# Microcontroller.net
KiCad netlist of a schematic drawn in Altium Designer
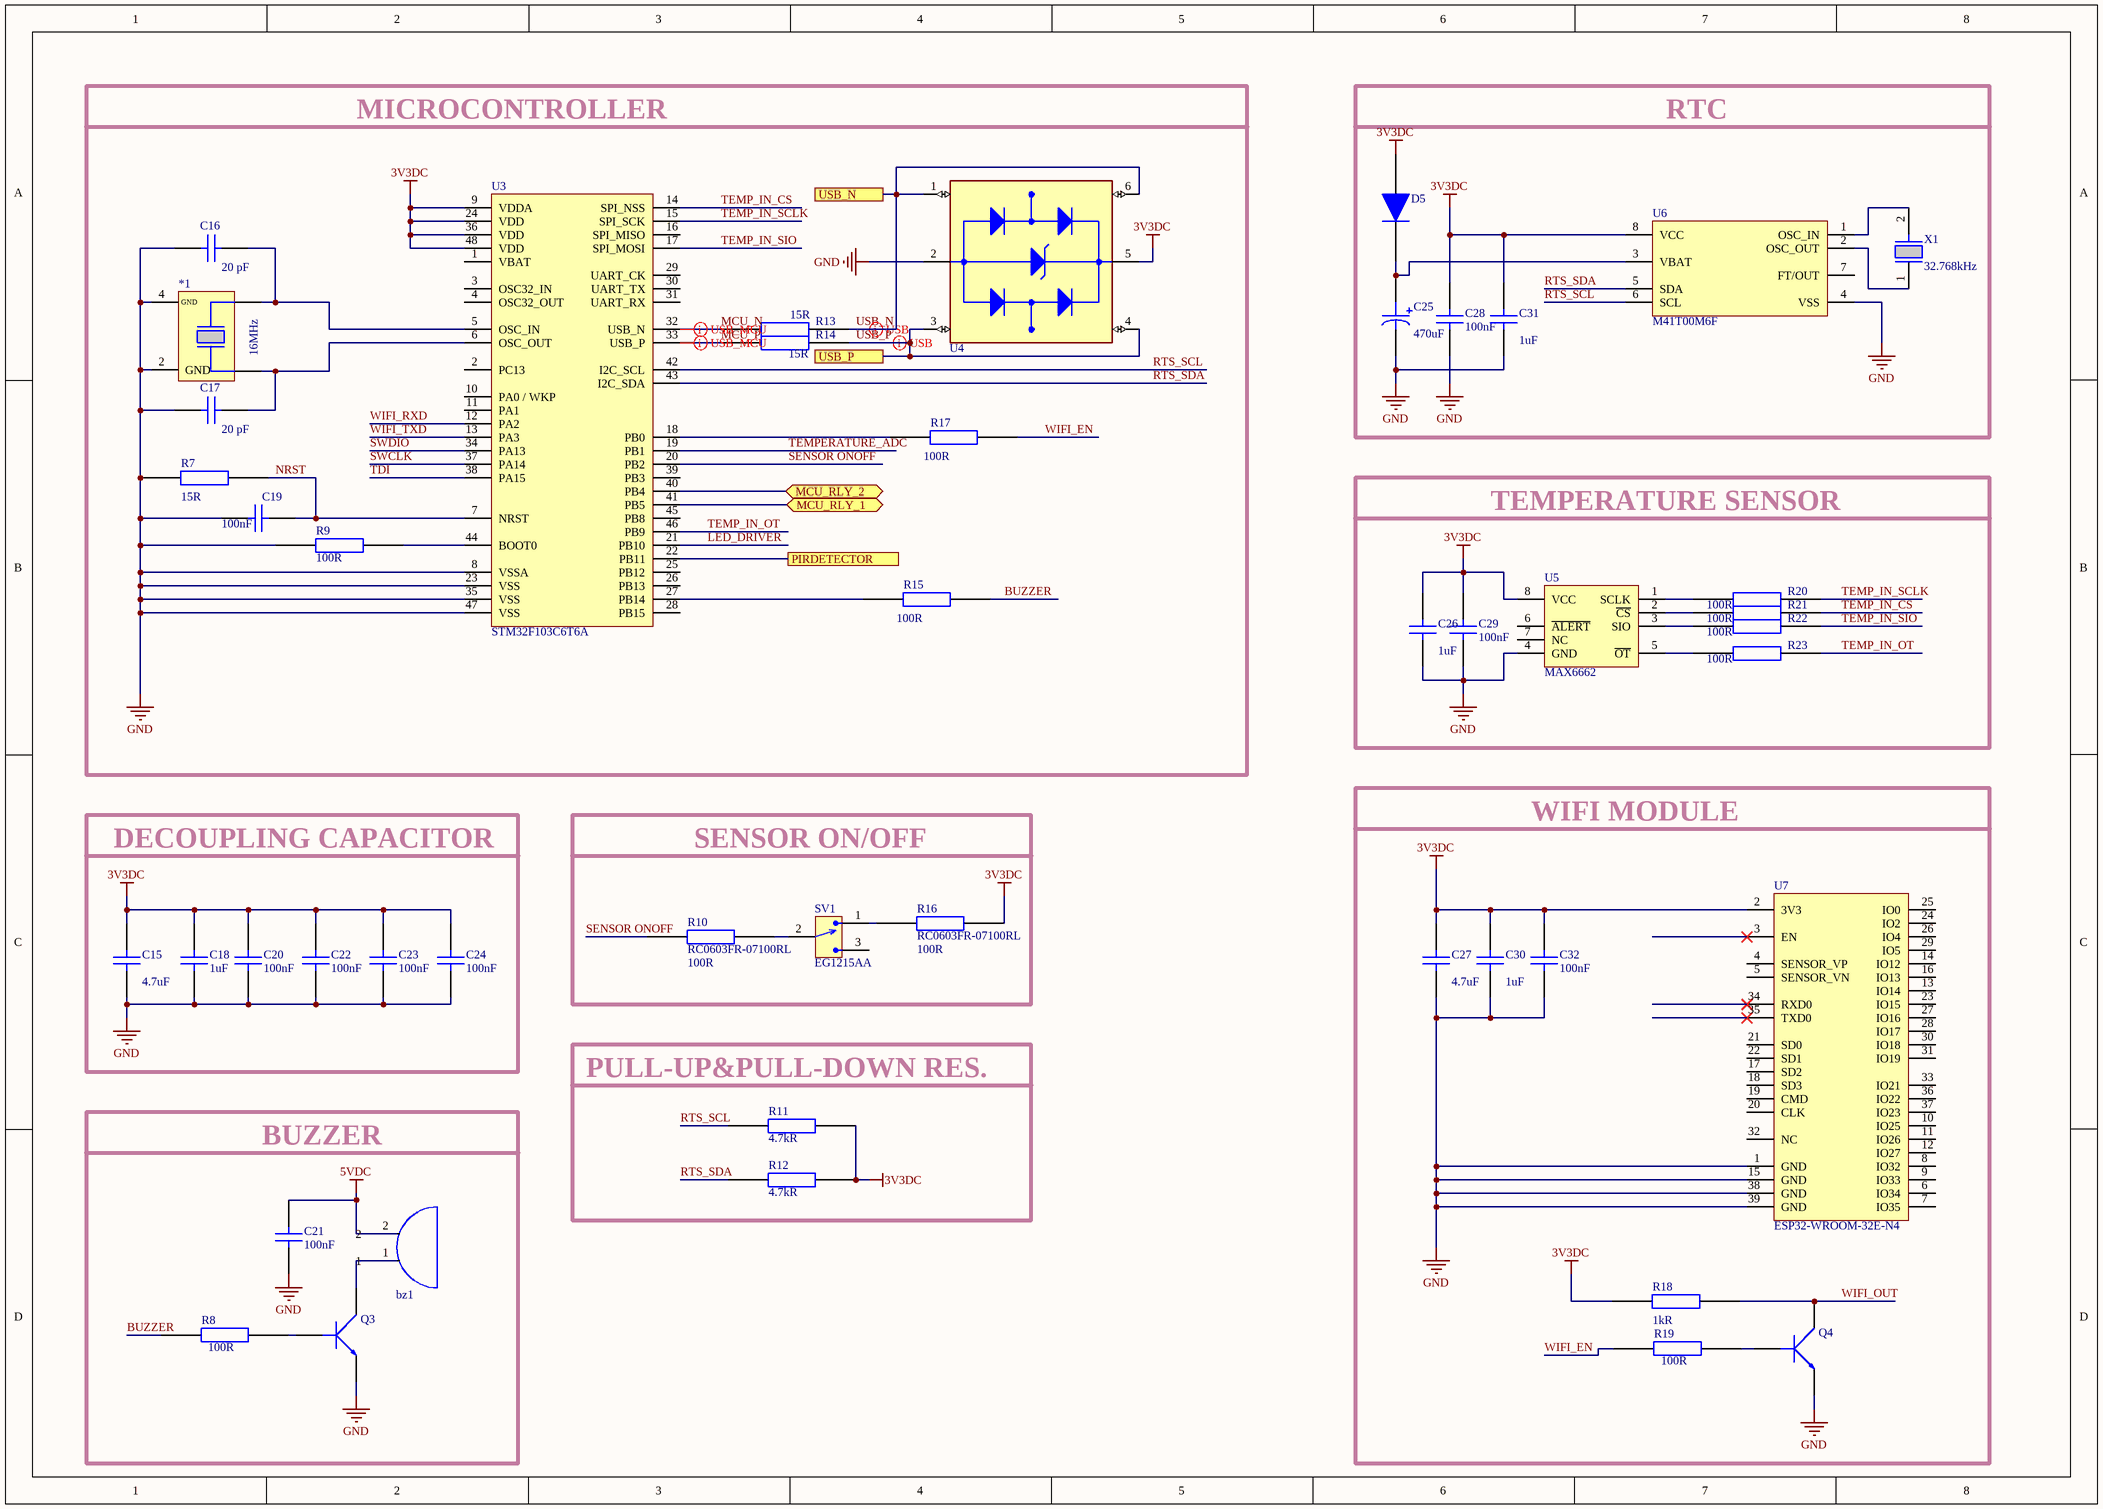
[diagram p0: Microcontroller.SchDoc]

(export (version "E")
  (design (tool "Eeschema 10.0.6"))
  (components
    (comp (ref "*1")
      (value "CRYSTAL 16MHz")
      (footprint "ECS")
      (description "Crystal 16MHz ±30ppm (Tol) ±50ppm (Stability) 20pF FUND 50Ohm 4-Pin Mini-SMD T/R")
      (fields
        (field (name "MANUFACTURER") "ECS International")
        (field (name "MANUFACTURER PART NUMBER") "ECS-160-20-30B-TR")
        (field (name "FREQUENCY") "16MHz")
        (field (name "DESIGNED BY") "Selenay")
      )
      (libsource (lib "LIBRARY1") (part "CRYSTAL 16MHz"))
    )
    (comp (ref "bz1")
      (value "2223-CMI-9605IC-0580T-ND")
      (footprint "CMI-9605IC")
      (description "Audio Buzzer Magnetic 3VDC 7VDC 30mA 5VDC 85dB 2600Hz to 2800Hz Through Hole Pin Box")
      (fields
        (field (name "MANUFACTURER") "CUI Devices")
        (field (name "MANUFACTURER PART NUMBER") "CMI-9605IC-0580T")
        (field (name "DESIGNED BY") "Selenay")
      )
      (libsource (lib "LIBRARY1") (part "2223-CMI-9605IC-0580T-ND"))
    )
    (comp (ref "C15")
      (value "4.7uF")
      (footprint "CAP_0805")
      (description "Multilayer Ceramic Capacitor, 4.7 uF, 25 V, ± 10%")
      (fields
        (field (name "MANUFACTURER") "Samsung")
        (field (name "MANUFACTURER PART NUMBER") "CL21A475KAQNNNE")
        (field (name "DESIGNED BY") "Selenay")
      )
      (libsource (lib "LIBRARY1") (part "CAP CER 4.7uF 0805"))
    )
    (comp (ref "C16")
      (value "CL10C200JB8NNNC")
      (footprint "CAP_0603")
      (description "Multilayer Ceramic Capacitor, 20 pF, 50 V, ± 5%")
      (fields
        (field (name "MANUFACTURER") "Samsung")
        (field (name "CAPATICANCE") "20 pF")
        (field (name "DESIGNED BY") "Selenay")
      )
      (libsource (lib "LIBRARY1") (part "CAP CER 20pF 0603"))
    )
    (comp (ref "C17")
      (value "CL10C200JB8NNNC")
      (footprint "CAP_0603")
      (description "Multilayer Ceramic Capacitor, 20 pF, 50 V, ± 5%")
      (fields
        (field (name "MANUFACTURER") "Samsung")
        (field (name "CAPATICANCE") "20 pF")
        (field (name "DESIGNED BY") "Selenay")
      )
      (libsource (lib "LIBRARY1") (part "CAP CER 20pF 0603"))
    )
    (comp (ref "C18")
      (value "1uF")
      (footprint "CAP_0805")
      (description "Multilayer Ceramic Capacitor, 1 uF, 50 V, ± 10%, X7R, 0805 [2012 Metric]")
      (fields
        (field (name "MANUFACTURER") "Samsung")
        (field (name "MANUFACTURER PART NUMBER") "CL21B105KBFNNNE")
        (field (name "DESIGNED BY") "Selenay")
      )
      (libsource (lib "LIBRARY1") (part "CAP CER 1uF 0805"))
    )
    (comp (ref "C19")
      (value "100nF")
      (footprint "CAP_0603")
      (description "Multilayer Ceramic Capacitor, 0.1 uF, 50 V, ± 10%, X7R, 0603 [1608 Metric]")
      (fields
        (field (name "MANUFACTURER") "KEMET")
        (field (name "MANUFACTURER PART NUMBER") "C0603C104K5RACTU")
        (field (name "DESIGNED BY") "Selenay")
      )
      (libsource (lib "LIBRARY1") (part "CAP CER 100nF 0603"))
    )
    (comp (ref "C20")
      (value "100nF")
      (footprint "CAP_0603")
      (description "Multilayer Ceramic Capacitor, 0.1 uF, 50 V, ± 10%, X7R, 0603 [1608 Metric]")
      (fields
        (field (name "MANUFACTURER") "KEMET")
        (field (name "MANUFACTURER PART NUMBER") "C0603C104K5RACTU")
        (field (name "DESIGNED BY") "Selenay")
      )
      (libsource (lib "LIBRARY1") (part "CAP CER 100nF 0603"))
    )
    (comp (ref "C21")
      (value "100nF")
      (footprint "CAP_0603")
      (description "Multilayer Ceramic Capacitor, 0.1 uF, 50 V, ± 10%, X7R, 0603 [1608 Metric]")
      (fields
        (field (name "MANUFACTURER") "KEMET")
        (field (name "MANUFACTURER PART NUMBER") "C0603C104K5RACTU")
        (field (name "DESIGNED BY") "Selenay")
      )
      (libsource (lib "LIBRARY1") (part "CAP CER 100nF 0603"))
    )
    (comp (ref "C22")
      (value "100nF")
      (footprint "CAP_0603")
      (description "Multilayer Ceramic Capacitor, 0.1 uF, 50 V, ± 10%, X7R, 0603 [1608 Metric]")
      (fields
        (field (name "MANUFACTURER") "KEMET")
        (field (name "MANUFACTURER PART NUMBER") "C0603C104K5RACTU")
        (field (name "DESIGNED BY") "Selenay")
      )
      (libsource (lib "LIBRARY1") (part "CAP CER 100nF 0603"))
    )
    (comp (ref "C23")
      (value "100nF")
      (footprint "CAP_0603")
      (description "Multilayer Ceramic Capacitor, 0.1 uF, 50 V, ± 10%, X7R, 0603 [1608 Metric]")
      (fields
        (field (name "MANUFACTURER") "KEMET")
        (field (name "MANUFACTURER PART NUMBER") "C0603C104K5RACTU")
        (field (name "DESIGNED BY") "Selenay")
      )
      (libsource (lib "LIBRARY1") (part "CAP CER 100nF 0603"))
    )
    (comp (ref "C24")
      (value "100nF")
      (footprint "CAP_0603")
      (description "Multilayer Ceramic Capacitor, 0.1 uF, 50 V, ± 10%, X7R, 0603 [1608 Metric]")
      (fields
        (field (name "MANUFACTURER") "KEMET")
        (field (name "MANUFACTURER PART NUMBER") "C0603C104K5RACTU")
        (field (name "DESIGNED BY") "Selenay")
      )
      (libsource (lib "LIBRARY1") (part "CAP CER 100nF 0603"))
    )
    (comp (ref "C25")
      (value "470uF")
      (footprint "CAP_EEVSRIES")
      (description "Cap Aluminum Lytic 470uF 25V 20% (10 X 10.2mm) SMD 850mA 2000h 105C T/R")
      (fields
        (field (name "MANUFACTURER") "KEMET")
        (field (name "MANUFACTURER PART NUMBER") "EEV477M025A9PAA")
        (field (name "DESIGNED BY") "Selenay")
      )
      (libsource (lib "LIBRARY1") (part "CAP ALU 470uF"))
    )
    (comp (ref "C26")
      (value "1uF")
      (footprint "CAP_0805")
      (description "Multilayer Ceramic Capacitor, 1 uF, 50 V, ± 10%, X7R, 0805 [2012 Metric]")
      (fields
        (field (name "MANUFACTURER") "Samsung")
        (field (name "MANUFACTURER PART NUMBER") "CL21B105KBFNNNE")
        (field (name "DESIGNED BY") "Selenay")
      )
      (libsource (lib "LIBRARY1") (part "CAP CER 1uF 0805"))
    )
    (comp (ref "C27")
      (value "4.7uF")
      (footprint "CAP_0805")
      (description "Multilayer Ceramic Capacitor, 4.7 uF, 25 V, ± 10%")
      (fields
        (field (name "MANUFACTURER") "Samsung")
        (field (name "MANUFACTURER PART NUMBER") "CL21A475KAQNNNE")
        (field (name "DESIGNED BY") "Selenay")
      )
      (libsource (lib "LIBRARY1") (part "CAP CER 4.7uF 0805"))
    )
    (comp (ref "C28")
      (value "100nF")
      (footprint "CAP_0603")
      (description "Multilayer Ceramic Capacitor, 0.1 uF, 50 V, ± 10%, X7R, 0603 [1608 Metric]")
      (fields
        (field (name "MANUFACTURER") "KEMET")
        (field (name "MANUFACTURER PART NUMBER") "C0603C104K5RACTU")
        (field (name "DESIGNED BY") "Selenay")
      )
      (libsource (lib "LIBRARY1") (part "CAP CER 100nF 0603"))
    )
    (comp (ref "C29")
      (value "100nF")
      (footprint "CAP_0603")
      (description "Multilayer Ceramic Capacitor, 0.1 uF, 50 V, ± 10%, X7R, 0603 [1608 Metric]")
      (fields
        (field (name "MANUFACTURER") "KEMET")
        (field (name "MANUFACTURER PART NUMBER") "C0603C104K5RACTU")
        (field (name "DESIGNED BY") "Selenay")
      )
      (libsource (lib "LIBRARY1") (part "CAP CER 100nF 0603"))
    )
    (comp (ref "C30")
      (value "1uF")
      (footprint "CAP_0805")
      (description "Multilayer Ceramic Capacitor, 1 uF, 50 V, ± 10%, X7R, 0805 [2012 Metric]")
      (fields
        (field (name "MANUFACTURER") "Samsung")
        (field (name "MANUFACTURER PART NUMBER") "CL21B105KBFNNNE")
        (field (name "DESIGNED BY") "Selenay")
      )
      (libsource (lib "LIBRARY1") (part "CAP CER 1uF 0805"))
    )
    (comp (ref "C31")
      (value "1uF")
      (footprint "CAP_0805")
      (description "Multilayer Ceramic Capacitor, 1 uF, 50 V, ± 10%, X7R, 0805 [2012 Metric]")
      (fields
        (field (name "MANUFACTURER") "Samsung")
        (field (name "MANUFACTURER PART NUMBER") "CL21B105KBFNNNE")
        (field (name "DESIGNED BY") "Selenay")
      )
      (libsource (lib "LIBRARY1") (part "CAP CER 1uF 0805"))
    )
    (comp (ref "C32")
      (value "100nF")
      (footprint "CAP_0603")
      (description "Multilayer Ceramic Capacitor, 0.1 uF, 50 V, ± 10%, X7R, 0603 [1608 Metric]")
      (fields
        (field (name "MANUFACTURER") "KEMET")
        (field (name "MANUFACTURER PART NUMBER") "C0603C104K5RACTU")
        (field (name "DESIGNED BY") "Selenay")
      )
      (libsource (lib "LIBRARY1") (part "CAP CER 100nF 0603"))
    )
    (comp (ref "D5")
      (value "1N4148WS-7-F")
      (footprint "SOD323F")
      (description "Small Signal Diode, 100V, SOD-323")
      (fields (field (name "MANUFACTURER") "Diodes") (field (name "VOLTAGE") "75V"))
      (libsource (lib "LIBRARY1") (part "1N4148WS"))
    )
    (comp (ref "Q3")
      (value "MMBT3904-7-F")
      (footprint "SOT-23F")
      (description "Transistor General Purpose BJT NPN 40 Volt 0.2A Automotive 3-Pin SOT-23")
      (fields (field (name "MANUFACTURER") "Diodes Zetex") (field (name "DESIGNED BY") "Selenay"))
      (libsource (lib "LIBRARY1") (part "MMBT3904-7-F"))
    )
    (comp (ref "Q4")
      (value "MMBT3904-7-F")
      (footprint "SOT-23F")
      (description "Transistor General Purpose BJT NPN 40 Volt 0.2A Automotive 3-Pin SOT-23")
      (fields (field (name "MANUFACTURER") "Diodes Zetex") (field (name "DESIGNED BY") "Selenay"))
      (libsource (lib "LIBRARY1") (part "MMBT3904-7-F"))
    )
    (comp (ref "R7")
      (value "15R")
      (footprint "RES_0603")
      (description "SMD Chip Resistor, 15 Ohm, ± 1%, 100 mW, 0603")
      (fields
        (field (name "MANUFACTURER") "Yageo")
        (field (name "MANUFACTURER PART NUMBER") "RC0603FR-0715RL")
        (field (name "DESIGNED BY") "Selenay")
      )
      (libsource (lib "LIBRARY1") (part "RES 15 OHM 0603"))
    )
    (comp (ref "R8")
      (value "100R")
      (footprint "RES_0603")
      (description "SMD Chip Resistor, 100 Ohm, ± 1%, 100 mW, 0603")
      (fields
        (field (name "MANUFACTURER") "Yageo")
        (field (name "MANUFACTURER PART NUMBER") "RC0603FR-07100RL")
        (field (name "DESIGNED BY") "Selenay")
      )
      (libsource (lib "LIBRARY1") (part "RES 100 OHM 0603"))
    )
    (comp (ref "R9")
      (value "100R")
      (footprint "RES_0603")
      (description "SMD Chip Resistor, 100 Ohm, ± 1%, 100 mW, 0603")
      (fields
        (field (name "MANUFACTURER") "Yageo")
        (field (name "MANUFACTURER PART NUMBER") "RC0603FR-07100RL")
        (field (name "DESIGNED BY") "Selenay")
      )
      (libsource (lib "") (part "RES 100 OHM 0603_1"))
    )
    (comp (ref "R10")
      (value "RC0603FR-07100RL")
      (footprint "RES_0603")
      (description "SMD Chip Resistor, 100 Ohm, ± 1%, 100 mW, 0603")
      (fields
        (field (name "MANUFACTURER") "Yageo")
        (field (name "TOLERANCE") "1%")
        (field (name "ALTIUM_VALUE") "100R")
        (field (name "DESIGNED BY") "Selenay")
      )
      (libsource (lib "") (part "RES 100 OHM 0603_1"))
    )
    (comp (ref "R11")
      (value "4.7kR")
      (footprint "RES_0603")
      (description "SMD Chip Resistor, 4.7 kOhm, ± 1%, 100 mW, 0603 [1608 Metric], Thick Film, General Purpose")
      (fields
        (field (name "MANUFACTURER") "Yageo")
        (field (name "MANUFACTURER PART NUMBER") "RC0603FR-074K7L")
      )
      (libsource (lib "LIBRARY1") (part "RES 4.7K OHM 0603"))
    )
    (comp (ref "R12")
      (value "4.7kR")
      (footprint "RES_0603")
      (description "SMD Chip Resistor, 4.7 kOhm, ± 1%, 100 mW, 0603 [1608 Metric], Thick Film, General Purpose")
      (fields
        (field (name "MANUFACTURER") "Yageo")
        (field (name "MANUFACTURER PART NUMBER") "RC0603FR-074K7L")
      )
      (libsource (lib "LIBRARY1") (part "RES 4.7K OHM 0603"))
    )
    (comp (ref "R13")
      (value "15R")
      (footprint "RES_0603")
      (description "SMD Chip Resistor, 15 Ohm, ± 1%, 100 mW, 0603")
      (fields
        (field (name "MANUFACTURER") "Yageo")
        (field (name "MANUFACTURER PART NUMBER") "RC0603FR-0715RL")
        (field (name "DESIGNED BY") "Selenay")
      )
      (libsource (lib "LIBRARY1") (part "RES 15 OHM 0603"))
    )
    (comp (ref "R14")
      (value "15R")
      (footprint "RES_0603")
      (description "SMD Chip Resistor, 15 Ohm, ± 1%, 100 mW, 0603")
      (fields
        (field (name "MANUFACTURER") "Yageo")
        (field (name "MANUFACTURER PART NUMBER") "RC0603FR-0715RL")
        (field (name "DESIGNED BY") "Selenay")
      )
      (libsource (lib "LIBRARY1") (part "RES 15 OHM 0603"))
    )
    (comp (ref "R15")
      (value "100R")
      (footprint "RES_0603")
      (description "SMD Chip Resistor, 100 Ohm, ± 1%, 100 mW, 0603")
      (fields
        (field (name "MANUFACTURER") "Yageo")
        (field (name "MANUFACTURER PART NUMBER") "RC0603FR-07100RL")
        (field (name "DESIGNED BY") "Selenay")
      )
      (libsource (lib "LIBRARY1") (part "RES 100 OHM 0603"))
    )
    (comp (ref "R16")
      (value "RC0603FR-07100RL")
      (footprint "RES_0603")
      (description "SMD Chip Resistor, 100 Ohm, ± 1%, 100 mW, 0603")
      (fields
        (field (name "MANUFACTURER") "Yageo")
        (field (name "TOLERANCE") "1%")
        (field (name "ALTIUM_VALUE") "100R")
        (field (name "DESIGNED BY") "Selenay")
      )
      (libsource (lib "LIBRARY1") (part "RES 100 OHM 0603"))
    )
    (comp (ref "R17")
      (value "100R")
      (footprint "RES_0603")
      (description "SMD Chip Resistor, 100 Ohm, ± 1%, 100 mW, 0603")
      (fields
        (field (name "MANUFACTURER") "Yageo")
        (field (name "MANUFACTURER PART NUMBER") "RC0603FR-07100RL")
        (field (name "DESIGNED BY") "Selenay")
      )
      (libsource (lib "LIBRARY1") (part "RES 100 OHM 0603"))
    )
    (comp (ref "R18")
      (value "1kR")
      (footprint "RES_0603")
      (description "SMD Chip Resistor, 1 kOhm, ± 1%, 100 mW, 0603 [1608 Metric], Thick Film, General Purpose")
      (fields
        (field (name "MANUFACTURER") "Yageo")
        (field (name "MANUFACTURER PART NUMBER") "RC0603FR-071KL")
        (field (name "DESIGNED BY") "Selenay")
      )
      (libsource (lib "LIBRARY1") (part "RES 1K OHM 0603"))
    )
    (comp (ref "R19")
      (value "100R")
      (footprint "RES_0603")
      (description "SMD Chip Resistor, 100 Ohm, ± 1%, 100 mW, 0603")
      (fields
        (field (name "MANUFACTURER") "Yageo")
        (field (name "MANUFACTURER PART NUMBER") "RC0603FR-07100RL")
        (field (name "DESIGNED BY") "Selenay")
      )
      (libsource (lib "LIBRARY1") (part "RES 100 OHM 0603"))
    )
    (comp (ref "R20")
      (value "100R")
      (footprint "RES_0603")
      (description "SMD Chip Resistor, 100 Ohm, ± 1%, 100 mW, 0603")
      (fields
        (field (name "MANUFACTURER") "Yageo")
        (field (name "MANUFACTURER PART NUMBER") "RC0603FR-07100RL")
        (field (name "DESIGNED BY") "Selenay")
      )
      (libsource (lib "LIBRARY1") (part "RES 100 OHM 0603"))
    )
    (comp (ref "R21")
      (value "100R")
      (footprint "RES_0603")
      (description "SMD Chip Resistor, 100 Ohm, ± 1%, 100 mW, 0603")
      (fields
        (field (name "MANUFACTURER") "Yageo")
        (field (name "MANUFACTURER PART NUMBER") "RC0603FR-07100RL")
        (field (name "DESIGNED BY") "Selenay")
      )
      (libsource (lib "LIBRARY1") (part "RES 100 OHM 0603"))
    )
    (comp (ref "R22")
      (value "100R")
      (footprint "RES_0603")
      (description "SMD Chip Resistor, 100 Ohm, ± 1%, 100 mW, 0603")
      (fields
        (field (name "MANUFACTURER") "Yageo")
        (field (name "MANUFACTURER PART NUMBER") "RC0603FR-07100RL")
        (field (name "DESIGNED BY") "Selenay")
      )
      (libsource (lib "LIBRARY1") (part "RES 100 OHM 0603"))
    )
    (comp (ref "R23")
      (value "100R")
      (footprint "RES_0603")
      (description "SMD Chip Resistor, 100 Ohm, ± 1%, 100 mW, 0603")
      (fields
        (field (name "MANUFACTURER") "Yageo")
        (field (name "MANUFACTURER PART NUMBER") "RC0603FR-07100RL")
        (field (name "DESIGNED BY") "Selenay")
      )
      (libsource (lib "LIBRARY1") (part "RES 100 OHM 0603"))
    )
    (comp (ref "SV1")
      (value "EG1215AA")
      (footprint "EG1215AA")
      (description "Slide Switch, SPDT, 0.025A, 24V, SMD")
      (fields (field (name "MANUFACTURER") "E-Switch") (field (name "DESIGNED BY") "Selenay"))
      (libsource (lib "LIBRARY1") (part "EG1215AA"))
    )
    (comp (ref "U3")
      (value "STM32F103C6T6A")
      (footprint "LQFP-48")
      (description "MCU 32-bit STM32F ARM Cortex M3 RISC 32KB Flash 2.5V/3.3V 48-Pin LQFP Tray")
      (fields (field (name "MANUFACTURER") "STMicroelectronics") (field (name "DESIGNER BY") "Selenay"))
      (libsource (lib "LIBRARY1") (part "STM32F103C6T6A"))
    )
    (comp (ref "U4")
      (value "USBLC6-2SC6")
      (footprint "SOT23-6L")
      (description "ESD Suppressor Diode Arrays Uni-Dir 15kV@Air Gap/8kV@Contact Disc 6-Pin SOT-23 T/R")
      (fields (field (name "MANUFACTURER") "STMicroelectronics") (field (name "DESIGNED BY") "Selenay"))
      (libsource (lib "LIBRARY1") (part "USB PROTECTION"))
    )
    (comp (ref "U5")
      (value "MAX6662")
      (footprint "SOIC8")
      (description "Temp Sensor Digital Serial (3-Wire, SPI) 8-Pin SOIC N Tube")
      (fields
        (field (name "MANUFACTURER") "Maxim")
        (field (name "MANUFACTURER PART NUMBER") "MAX6662MSA+")
        (field (name "DESIGNED BY") "Selenay")
      )
      (libsource (lib "LIBRARY1") (part "MAX6662"))
    )
    (comp (ref "U6")
      (value "M41T00M6F")
      (footprint "SOIC8")
      (description "Real-time Clocks Clock/Calendar I2C, 2-Wire Serial 70uA @ 2V ~ 5.5V SOIC-8_150mil RoHS")
      (fields (field (name "MANUFACTURER") "STMicroelectronics") (field (name "DESIGNED BY") "SELENAY"))
      (libsource (lib "LIBRARY1") (part "M41T00M6F"))
    )
    (comp (ref "U7")
      (value "ESP32-WROOM-32E-N4")
      (footprint "ESP32-32E")
      (description "SMD module, ESP32-D0WD-V3, ESP32 ECO V3, 4 MB SPI flash, PCB antenna")
      (fields
        (field (name "MANUFACTURER") "Espressif Systems")
        (field (name "MANUFACTURER PART NUMBER") "ESP32-WROOM-32E(M113EH3200PH3Q0)")
        (field (name "DESIGNED BY") "SELENAY")
      )
      (libsource (lib "LIBRARY1") (part "ESP32-WROOM-32E-N4"))
    )
    (comp (ref "X1")
      (value "ABS05-32.768KHZ-T")
      (footprint "ABS05")
      (description "Crystal 0.032768MHz ±20ppm (Tol) 12.5pF Flexural 90000Ohm 2-Pin CSMD T/R")
      (fields
        (field (name "MANUFACTURER") "Abracon")
        (field (name "TOLERANCE") "20ppm")
        (field (name "FREQUENCY") "32.768kHz")
        (field (name "DESIGNED BY") "Selenay")
      )
      (libsource (lib "LIBRARY1") (part "CRYSTAL 32768KHz"))
    )
  )
  (nets
    (net (code "1") (name "/BUZZER") (class "Default")
      (node (ref "R15") (pin "2") (pinfunction "1_2") (pintype "passive"))
      (node (ref "R8") (pin "1") (pinfunction "1_1") (pintype "passive"))
    )
    (net (code "2") (name "/LED_DRIVER") (class "Default")
      (node (ref "U3") (pin "21") (pinfunction "PB10_21") (pintype "passive"))
    )
    (net (code "3") (name "/MCU_N") (class "Default")
      (node (ref "R13") (pin "1") (pinfunction "1_1") (pintype "passive"))
      (node (ref "U3") (pin "32") (pinfunction "USB_N_32") (pintype "passive"))
    )
    (net (code "4") (name "/MCU_P") (class "Default")
      (node (ref "R14") (pin "1") (pinfunction "1_1") (pintype "passive"))
      (node (ref "U3") (pin "33") (pinfunction "USB_P_33") (pintype "passive"))
    )
    (net (code "5") (name "/MCU_RLY_1") (class "Default")
      (node (ref "U3") (pin "41") (pinfunction "PB5_41") (pintype "passive"))
    )
    (net (code "6") (name "/MCU_RLY_2") (class "Default")
      (node (ref "U3") (pin "40") (pinfunction "PB4_40") (pintype "passive"))
    )
    (net (code "7") (name "/NRST") (class "Default")
      (node (ref "C19") (pin "2") (pinfunction "2_2") (pintype "passive"))
      (node (ref "R7") (pin "2") (pinfunction "1_2") (pintype "passive"))
      (node (ref "U3") (pin "7") (pinfunction "NRST_7") (pintype "passive"))
    )
    (net (code "8") (name "/PIRDETECTOR") (class "Default")
      (node (ref "U3") (pin "22") (pinfunction "PB11_22") (pintype "passive"))
    )
    (net (code "9") (name "/RTS_SCL") (class "Default")
      (node (ref "R11") (pin "2") (pinfunction "1_2") (pintype "passive"))
      (node (ref "U3") (pin "42") (pinfunction "I2C_SCL_42") (pintype "passive"))
      (node (ref "U6") (pin "6") (pinfunction "SCL_6") (pintype "passive"))
    )
    (net (code "10") (name "/RTS_SDA") (class "Default")
      (node (ref "R12") (pin "2") (pinfunction "1_2") (pintype "passive"))
      (node (ref "U3") (pin "43") (pinfunction "I2C_SDA_43") (pintype "passive"))
      (node (ref "U6") (pin "5") (pinfunction "SDA_5") (pintype "passive"))
    )
    (net (code "11") (name "/SENSOR ONOFF") (class "Default")
      (node (ref "R10") (pin "2") (pinfunction "1_2") (pintype "passive"))
      (node (ref "U3") (pin "20") (pinfunction "PB2_20") (pintype "passive"))
    )
    (net (code "12") (name "/SWCLK") (class "Default")
      (node (ref "U3") (pin "37") (pinfunction "PA14_37") (pintype "passive"))
    )
    (net (code "13") (name "/SWDIO") (class "Default")
      (node (ref "U3") (pin "34") (pinfunction "PA13_34") (pintype "passive"))
    )
    (net (code "14") (name "/TDI") (class "Default")
      (node (ref "U3") (pin "38") (pinfunction "PA15_38") (pintype "passive"))
    )
    (net (code "15") (name "/TEMPERATURE_ADC") (class "Default")
      (node (ref "U3") (pin "19") (pinfunction "PB1_19") (pintype "passive"))
    )
    (net (code "16") (name "/TEMP_IN_CS") (class "Default")
      (node (ref "R21") (pin "2") (pinfunction "1_2") (pintype "passive"))
      (node (ref "U3") (pin "14") (pinfunction "SPI_NSS_14") (pintype "passive"))
    )
    (net (code "17") (name "/TEMP_IN_OT") (class "Default")
      (node (ref "R23") (pin "2") (pinfunction "1_2") (pintype "passive"))
      (node (ref "U3") (pin "46") (pinfunction "PB9_46") (pintype "passive"))
    )
    (net (code "18") (name "/TEMP_IN_SCLK") (class "Default")
      (node (ref "R20") (pin "2") (pinfunction "1_2") (pintype "passive"))
      (node (ref "U3") (pin "15") (pinfunction "SPI_SCK_15") (pintype "passive"))
    )
    (net (code "19") (name "/TEMP_IN_SIO") (class "Default")
      (node (ref "R22") (pin "2") (pinfunction "1_2") (pintype "passive"))
      (node (ref "U3") (pin "17") (pinfunction "SPI_MOSI_17") (pintype "passive"))
    )
    (net (code "20") (name "/USB_N") (class "Default")
      (node (ref "R13") (pin "2") (pinfunction "1_2") (pintype "passive"))
      (node (ref "U4") (pin "1") (pinfunction "I/O1_IN_1") (pintype "bidirectional"))
      (node (ref "U4") (pin "6") (pinfunction "I/O1_OUT_6") (pintype "bidirectional"))
    )
    (net (code "21") (name "/USB_P") (class "Default")
      (node (ref "R14") (pin "2") (pinfunction "1_2") (pintype "passive"))
      (node (ref "U4") (pin "3") (pinfunction "I/O2_IN_3") (pintype "bidirectional"))
      (node (ref "U4") (pin "4") (pinfunction "I/O2_OUT_4") (pintype "bidirectional"))
    )
    (net (code "22") (name "/WIFI_EN") (class "Default")
      (node (ref "R17") (pin "2") (pinfunction "1_2") (pintype "passive"))
      (node (ref "R19") (pin "1") (pinfunction "1_1") (pintype "passive"))
    )
    (net (code "23") (name "/WIFI_OUT") (class "Default")
      (node (ref "Q4") (pin "3") (pinfunction "C_3") (pintype "passive"))
      (node (ref "R18") (pin "2") (pinfunction "1_2") (pintype "passive"))
    )
    (net (code "24") (name "/WIFI_RXD") (class "Default")
      (node (ref "U3") (pin "12") (pinfunction "PA2_12") (pintype "passive"))
    )
    (net (code "25") (name "/WIFI_TXD") (class "Default")
      (node (ref "U3") (pin "13") (pinfunction "PA3_13") (pintype "passive"))
    )
    (net (code "26") (name "3V3DC") (class "Default")
      (node (ref "C15") (pin "2") (pinfunction "2_2") (pintype "passive"))
      (node (ref "C18") (pin "1") (pinfunction "1_1") (pintype "passive"))
      (node (ref "C20") (pin "1") (pinfunction "1_1") (pintype "passive"))
      (node (ref "C22") (pin "1") (pinfunction "1_1") (pintype "passive"))
      (node (ref "C23") (pin "1") (pinfunction "1_1") (pintype "passive"))
      (node (ref "C24") (pin "1") (pinfunction "1_1") (pintype "passive"))
      (node (ref "C26") (pin "2") (pinfunction "2_2") (pintype "passive"))
      (node (ref "C27") (pin "2") (pinfunction "2_2") (pintype "passive"))
      (node (ref "C28") (pin "2") (pinfunction "2_2") (pintype "passive"))
      (node (ref "C29") (pin "2") (pinfunction "2_2") (pintype "passive"))
      (node (ref "C30") (pin "2") (pinfunction "2_2") (pintype "passive"))
      (node (ref "C31") (pin "2") (pinfunction "2_2") (pintype "passive"))
      (node (ref "C32") (pin "2") (pinfunction "2_2") (pintype "passive"))
      (node (ref "D5") (pin "2") (pinfunction "2_2") (pintype "passive"))
      (node (ref "R11") (pin "1") (pinfunction "1_1") (pintype "passive"))
      (node (ref "R12") (pin "1") (pinfunction "1_1") (pintype "passive"))
      (node (ref "R16") (pin "2") (pinfunction "1_2") (pintype "passive"))
      (node (ref "R18") (pin "1") (pinfunction "1_1") (pintype "passive"))
      (node (ref "U3") (pin "24") (pinfunction "VDD_24") (pintype "passive"))
      (node (ref "U3") (pin "36") (pinfunction "VDD_36") (pintype "passive"))
      (node (ref "U3") (pin "48") (pinfunction "VDD_48") (pintype "passive"))
      (node (ref "U3") (pin "9") (pinfunction "VDDA_9") (pintype "passive"))
      (node (ref "U4") (pin "5") (pinfunction "VBUS_5") (pintype "power_in"))
      (node (ref "U5") (pin "8") (pinfunction "VCC_8") (pintype "passive"))
      (node (ref "U6") (pin "8") (pinfunction "VCC_8") (pintype "passive"))
      (node (ref "U7") (pin "2") (pinfunction "3V3_2") (pintype "passive"))
    )
    (net (code "27") (name "5VDC") (class "Default")
      (node (ref "C21") (pin "2") (pinfunction "2_2") (pintype "passive"))
      (node (ref "bz1") (pin "2") (pinfunction "2_2") (pintype "passive"))
    )
    (net (code "28") (name "GND") (class "Default")
      (node (ref "*1") (pin "2") (pinfunction "GND_2") (pintype "passive"))
      (node (ref "*1") (pin "4") (pinfunction "GND_4") (pintype "passive"))
      (node (ref "C15") (pin "1") (pinfunction "1_1") (pintype "passive"))
      (node (ref "C16") (pin "1") (pinfunction "1_1") (pintype "passive"))
      (node (ref "C17") (pin "1") (pinfunction "1_1") (pintype "passive"))
      (node (ref "C18") (pin "2") (pinfunction "2_2") (pintype "passive"))
      (node (ref "C19") (pin "1") (pinfunction "1_1") (pintype "passive"))
      (node (ref "C20") (pin "2") (pinfunction "2_2") (pintype "passive"))
      (node (ref "C21") (pin "1") (pinfunction "1_1") (pintype "passive"))
      (node (ref "C22") (pin "2") (pinfunction "2_2") (pintype "passive"))
      (node (ref "C23") (pin "2") (pinfunction "2_2") (pintype "passive"))
      (node (ref "C24") (pin "2") (pinfunction "2_2") (pintype "passive"))
      (node (ref "C25") (pin "2") (pinfunction "2_2") (pintype "passive"))
      (node (ref "C26") (pin "1") (pinfunction "1_1") (pintype "passive"))
      (node (ref "C27") (pin "1") (pinfunction "1_1") (pintype "passive"))
      (node (ref "C28") (pin "1") (pinfunction "1_1") (pintype "passive"))
      (node (ref "C29") (pin "1") (pinfunction "1_1") (pintype "passive"))
      (node (ref "C30") (pin "1") (pinfunction "1_1") (pintype "passive"))
      (node (ref "C31") (pin "1") (pinfunction "1_1") (pintype "passive"))
      (node (ref "C32") (pin "1") (pinfunction "1_1") (pintype "passive"))
      (node (ref "Q3") (pin "2") (pinfunction "E_2") (pintype "passive"))
      (node (ref "Q4") (pin "2") (pinfunction "E_2") (pintype "passive"))
      (node (ref "R7") (pin "1") (pinfunction "1_1") (pintype "passive"))
      (node (ref "R9") (pin "2") (pinfunction "1_2") (pintype "passive"))
      (node (ref "U3") (pin "23") (pinfunction "VSS_23") (pintype "passive"))
      (node (ref "U3") (pin "35") (pinfunction "VSS_35") (pintype "passive"))
      (node (ref "U3") (pin "47") (pinfunction "VSS_47") (pintype "passive"))
      (node (ref "U3") (pin "8") (pinfunction "VSSA_8") (pintype "passive"))
      (node (ref "U4") (pin "2") (pinfunction "GND_2") (pintype "power_in"))
      (node (ref "U5") (pin "4") (pinfunction "GND_4") (pintype "passive"))
      (node (ref "U6") (pin "4") (pinfunction "VSS_4") (pintype "passive"))
      (node (ref "U7") (pin "1") (pinfunction "GND_1") (pintype "passive"))
      (node (ref "U7") (pin "15") (pinfunction "GND_15") (pintype "passive"))
      (node (ref "U7") (pin "38") (pinfunction "GND_38") (pintype "passive"))
      (node (ref "U7") (pin "39") (pinfunction "GND_39") (pintype "passive"))
    )
    (net (code "29") (name "Net-(Q3-B)") (class "Default")
      (node (ref "Q3") (pin "1") (pinfunction "B_1") (pintype "passive"))
      (node (ref "R8") (pin "2") (pinfunction "1_2") (pintype "passive"))
    )
    (net (code "30") (name "Net-(Q3-C)") (class "Default")
      (node (ref "Q3") (pin "3") (pinfunction "C_3") (pintype "passive"))
      (node (ref "bz1") (pin "1") (pinfunction "1_1") (pintype "passive"))
    )
    (net (code "31") (name "Net-(Q4-B)") (class "Default")
      (node (ref "Q4") (pin "1") (pinfunction "B_1") (pintype "passive"))
      (node (ref "R19") (pin "2") (pinfunction "1_2") (pintype "passive"))
    )
    (net (code "32") (name "Net-(R10-Pad1)") (class "Default")
      (node (ref "R10") (pin "1") (pinfunction "1_1") (pintype "passive"))
      (node (ref "SV1") (pin "2") (pinfunction "2_2") (pintype "passive"))
    )
    (net (code "33") (name "Net-(R16-Pad1)") (class "Default")
      (node (ref "R16") (pin "1") (pinfunction "1_1") (pintype "passive"))
      (node (ref "SV1") (pin "1") (pinfunction "1_1") (pintype "passive"))
    )
    (net (code "34") (name "Net-(U3-BOOT0)") (class "Default")
      (node (ref "R9") (pin "1") (pinfunction "1_1") (pintype "passive"))
      (node (ref "U3") (pin "44") (pinfunction "BOOT0_44") (pintype "passive"))
    )
    (net (code "35") (name "Net-(U3-OSC_IN)") (class "Default")
      (node (ref "*1") (pin "3") (pinfunction "3_3") (pintype "passive"))
      (node (ref "C16") (pin "2") (pinfunction "2_2") (pintype "passive"))
      (node (ref "U3") (pin "5") (pinfunction "OSC_IN_5") (pintype "passive"))
    )
    (net (code "36") (name "Net-(U3-OSC_OUT)") (class "Default")
      (node (ref "*1") (pin "1") (pinfunction "1_1") (pintype "passive"))
      (node (ref "C17") (pin "2") (pinfunction "2_2") (pintype "passive"))
      (node (ref "U3") (pin "6") (pinfunction "OSC_OUT_6") (pintype "passive"))
    )
    (net (code "37") (name "Net-(U3-PB0)") (class "Default")
      (node (ref "R17") (pin "1") (pinfunction "1_1") (pintype "passive"))
      (node (ref "U3") (pin "18") (pinfunction "PB0_18") (pintype "passive"))
    )
    (net (code "38") (name "Net-(U3-PB14)") (class "Default")
      (node (ref "R15") (pin "1") (pinfunction "1_1") (pintype "passive"))
      (node (ref "U3") (pin "27") (pinfunction "PB14_27") (pintype "passive"))
    )
    (net (code "39") (name "Net-(U5-SCLK)") (class "Default")
      (node (ref "R20") (pin "1") (pinfunction "1_1") (pintype "passive"))
      (node (ref "U5") (pin "1") (pinfunction "SCLK_1") (pintype "passive"))
    )
    (net (code "40") (name "Net-(U5-SIO)") (class "Default")
      (node (ref "R22") (pin "1") (pinfunction "1_1") (pintype "passive"))
      (node (ref "U5") (pin "3") (pinfunction "SIO_3") (pintype "passive"))
    )
    (net (code "41") (name "Net-(U5-~{CS})") (class "Default")
      (node (ref "R21") (pin "1") (pinfunction "1_1") (pintype "passive"))
      (node (ref "U5") (pin "2") (pinfunction "~{CS}_2") (pintype "passive"))
    )
    (net (code "42") (name "Net-(U5-~{OT})") (class "Default")
      (node (ref "R23") (pin "1") (pinfunction "1_1") (pintype "passive"))
      (node (ref "U5") (pin "5") (pinfunction "~{OT}_5") (pintype "passive"))
    )
    (net (code "43") (name "Net-(U6-OSC_IN)") (class "Default")
      (node (ref "U6") (pin "1") (pinfunction "OSC_IN_1") (pintype "passive"))
      (node (ref "X1") (pin "2") (pinfunction "2_2") (pintype "passive"))
    )
    (net (code "44") (name "Net-(U6-OSC_OUT)") (class "Default")
      (node (ref "U6") (pin "2") (pinfunction "OSC_OUT_2") (pintype "passive"))
      (node (ref "X1") (pin "1") (pinfunction "1_1") (pintype "passive"))
    )
    (net (code "45") (name "Net-(U6-VBAT)") (class "Default")
      (node (ref "C25") (pin "1") (pinfunction "1_1") (pintype "passive"))
      (node (ref "D5") (pin "1") (pinfunction "1_1") (pintype "passive"))
      (node (ref "U6") (pin "3") (pinfunction "VBAT_3") (pintype "passive"))
    )
    (net (code "46") (name "unconnected-(SV1-Pad3)") (class "Default")
      (node (ref "SV1") (pin "3") (pinfunction "3_3") (pintype "passive"))
    )
    (net (code "47") (name "unconnected-(U3-OSC32_IN-Pad3)") (class "Default")
      (node (ref "U3") (pin "3") (pinfunction "OSC32_IN_3") (pintype "passive"))
    )
    (net (code "48") (name "unconnected-(U3-OSC32_OUT-Pad4)") (class "Default")
      (node (ref "U3") (pin "4") (pinfunction "OSC32_OUT_4") (pintype "passive"))
    )
    (net (code "49") (name "unconnected-(U3-PA0_{slash}_WKP-Pad10)") (class "Default")
      (node (ref "U3") (pin "10") (pinfunction "PA0_/_WKP_10") (pintype "passive"))
    )
    (net (code "50") (name "unconnected-(U3-PA1-Pad11)") (class "Default")
      (node (ref "U3") (pin "11") (pinfunction "PA1_11") (pintype "passive"))
    )
    (net (code "51") (name "unconnected-(U3-PB3-Pad39)") (class "Default")
      (node (ref "U3") (pin "39") (pinfunction "PB3_39") (pintype "passive"))
    )
    (net (code "52") (name "unconnected-(U3-PB8-Pad45)") (class "Default")
      (node (ref "U3") (pin "45") (pinfunction "PB8_45") (pintype "passive"))
    )
    (net (code "53") (name "unconnected-(U3-PB12-Pad25)") (class "Default")
      (node (ref "U3") (pin "25") (pinfunction "PB12_25") (pintype "passive"))
    )
    (net (code "54") (name "unconnected-(U3-PB13-Pad26)") (class "Default")
      (node (ref "U3") (pin "26") (pinfunction "PB13_26") (pintype "passive"))
    )
    (net (code "55") (name "unconnected-(U3-PB15-Pad28)") (class "Default")
      (node (ref "U3") (pin "28") (pinfunction "PB15_28") (pintype "passive"))
    )
    (net (code "56") (name "unconnected-(U3-PC13-Pad2)") (class "Default")
      (node (ref "U3") (pin "2") (pinfunction "PC13_2") (pintype "passive"))
    )
    (net (code "57") (name "unconnected-(U3-SPI_MISO-Pad16)") (class "Default")
      (node (ref "U3") (pin "16") (pinfunction "SPI_MISO_16") (pintype "passive"))
    )
    (net (code "58") (name "unconnected-(U3-UART_CK-Pad29)") (class "Default")
      (node (ref "U3") (pin "29") (pinfunction "UART_CK_29") (pintype "passive"))
    )
    (net (code "59") (name "unconnected-(U3-UART_RX-Pad31)") (class "Default")
      (node (ref "U3") (pin "31") (pinfunction "UART_RX_31") (pintype "passive"))
    )
    (net (code "60") (name "unconnected-(U3-UART_TX-Pad30)") (class "Default")
      (node (ref "U3") (pin "30") (pinfunction "UART_TX_30") (pintype "passive"))
    )
    (net (code "61") (name "unconnected-(U3-VBAT-Pad1)") (class "Default")
      (node (ref "U3") (pin "1") (pinfunction "VBAT_1") (pintype "passive"))
    )
    (net (code "62") (name "unconnected-(U5-NC-Pad7)") (class "Default")
      (node (ref "U5") (pin "7") (pinfunction "NC_7") (pintype "passive"))
    )
    (net (code "63") (name "unconnected-(U5-~{ALERT}-Pad6)") (class "Default")
      (node (ref "U5") (pin "6") (pinfunction "~{ALERT}_6") (pintype "passive"))
    )
    (net (code "64") (name "unconnected-(U6-FT{slash}OUT-Pad7)") (class "Default")
      (node (ref "U6") (pin "7") (pinfunction "FT/OUT_7") (pintype "passive"))
    )
    (net (code "65") (name "unconnected-(U7-CLK-Pad20)") (class "Default")
      (node (ref "U7") (pin "20") (pinfunction "CLK_20") (pintype "passive"))
    )
    (net (code "66") (name "unconnected-(U7-CMD-Pad19)") (class "Default")
      (node (ref "U7") (pin "19") (pinfunction "CMD_19") (pintype "passive"))
    )
    (net (code "67") (name "unconnected-(U7-EN-Pad3)") (class "Default")
      (node (ref "U7") (pin "3") (pinfunction "EN_3") (pintype "passive+no_connect"))
    )
    (net (code "68") (name "unconnected-(U7-IO0-Pad25)") (class "Default")
      (node (ref "U7") (pin "25") (pinfunction "IO0_25") (pintype "passive"))
    )
    (net (code "69") (name "unconnected-(U7-IO2-Pad24)") (class "Default")
      (node (ref "U7") (pin "24") (pinfunction "IO2_24") (pintype "passive"))
    )
    (net (code "70") (name "unconnected-(U7-IO4-Pad26)") (class "Default")
      (node (ref "U7") (pin "26") (pinfunction "IO4_26") (pintype "passive"))
    )
    (net (code "71") (name "unconnected-(U7-IO5-Pad29)") (class "Default")
      (node (ref "U7") (pin "29") (pinfunction "IO5_29") (pintype "passive"))
    )
    (net (code "72") (name "unconnected-(U7-IO12-Pad14)") (class "Default")
      (node (ref "U7") (pin "14") (pinfunction "IO12_14") (pintype "passive"))
    )
    (net (code "73") (name "unconnected-(U7-IO13-Pad16)") (class "Default")
      (node (ref "U7") (pin "16") (pinfunction "IO13_16") (pintype "passive"))
    )
    (net (code "74") (name "unconnected-(U7-IO14-Pad13)") (class "Default")
      (node (ref "U7") (pin "13") (pinfunction "IO14_13") (pintype "passive"))
    )
    (net (code "75") (name "unconnected-(U7-IO15-Pad23)") (class "Default")
      (node (ref "U7") (pin "23") (pinfunction "IO15_23") (pintype "passive"))
    )
    (net (code "76") (name "unconnected-(U7-IO16-Pad27)") (class "Default")
      (node (ref "U7") (pin "27") (pinfunction "IO16_27") (pintype "passive"))
    )
    (net (code "77") (name "unconnected-(U7-IO17-Pad28)") (class "Default")
      (node (ref "U7") (pin "28") (pinfunction "IO17_28") (pintype "passive"))
    )
    (net (code "78") (name "unconnected-(U7-IO18-Pad30)") (class "Default")
      (node (ref "U7") (pin "30") (pinfunction "IO18_30") (pintype "passive"))
    )
    (net (code "79") (name "unconnected-(U7-IO19-Pad31)") (class "Default")
      (node (ref "U7") (pin "31") (pinfunction "IO19_31") (pintype "passive"))
    )
    (net (code "80") (name "unconnected-(U7-IO21-Pad33)") (class "Default")
      (node (ref "U7") (pin "33") (pinfunction "IO21_33") (pintype "passive"))
    )
    (net (code "81") (name "unconnected-(U7-IO22-Pad36)") (class "Default")
      (node (ref "U7") (pin "36") (pinfunction "IO22_36") (pintype "passive"))
    )
    (net (code "82") (name "unconnected-(U7-IO23-Pad37)") (class "Default")
      (node (ref "U7") (pin "37") (pinfunction "IO23_37") (pintype "passive"))
    )
    (net (code "83") (name "unconnected-(U7-IO25-Pad10)") (class "Default")
      (node (ref "U7") (pin "10") (pinfunction "IO25_10") (pintype "passive"))
    )
    (net (code "84") (name "unconnected-(U7-IO26-Pad11)") (class "Default")
      (node (ref "U7") (pin "11") (pinfunction "IO26_11") (pintype "passive"))
    )
    (net (code "85") (name "unconnected-(U7-IO27-Pad12)") (class "Default")
      (node (ref "U7") (pin "12") (pinfunction "IO27_12") (pintype "passive"))
    )
    (net (code "86") (name "unconnected-(U7-IO32-Pad8)") (class "Default")
      (node (ref "U7") (pin "8") (pinfunction "IO32_8") (pintype "passive"))
    )
    (net (code "87") (name "unconnected-(U7-IO33-Pad9)") (class "Default")
      (node (ref "U7") (pin "9") (pinfunction "IO33_9") (pintype "passive"))
    )
    (net (code "88") (name "unconnected-(U7-IO34-Pad6)") (class "Default")
      (node (ref "U7") (pin "6") (pinfunction "IO34_6") (pintype "passive"))
    )
    (net (code "89") (name "unconnected-(U7-IO35-Pad7)") (class "Default")
      (node (ref "U7") (pin "7") (pinfunction "IO35_7") (pintype "passive"))
    )
    (net (code "90") (name "unconnected-(U7-NC-Pad32)") (class "Default")
      (node (ref "U7") (pin "32") (pinfunction "NC_32") (pintype "passive"))
    )
    (net (code "91") (name "unconnected-(U7-RXD0-Pad34)") (class "Default")
      (node (ref "U7") (pin "34") (pinfunction "RXD0_34") (pintype "passive+no_connect"))
    )
    (net (code "92") (name "unconnected-(U7-SD0-Pad21)") (class "Default")
      (node (ref "U7") (pin "21") (pinfunction "SD0_21") (pintype "passive"))
    )
    (net (code "93") (name "unconnected-(U7-SD1-Pad22)") (class "Default")
      (node (ref "U7") (pin "22") (pinfunction "SD1_22") (pintype "passive"))
    )
    (net (code "94") (name "unconnected-(U7-SD2-Pad17)") (class "Default")
      (node (ref "U7") (pin "17") (pinfunction "SD2_17") (pintype "passive"))
    )
    (net (code "95") (name "unconnected-(U7-SD3-Pad18)") (class "Default")
      (node (ref "U7") (pin "18") (pinfunction "SD3_18") (pintype "passive"))
    )
    (net (code "96") (name "unconnected-(U7-SENSOR_VN-Pad5)") (class "Default")
      (node (ref "U7") (pin "5") (pinfunction "SENSOR_VN_5") (pintype "passive"))
    )
    (net (code "97") (name "unconnected-(U7-SENSOR_VP-Pad4)") (class "Default")
      (node (ref "U7") (pin "4") (pinfunction "SENSOR_VP_4") (pintype "passive"))
    )
    (net (code "98") (name "unconnected-(U7-TXD0-Pad35)") (class "Default")
      (node (ref "U7") (pin "35") (pinfunction "TXD0_35") (pintype "passive+no_connect"))
    )
  )
)
